# module_buzzer.net
KiCad netlist of a schematic drawn in EAGLE
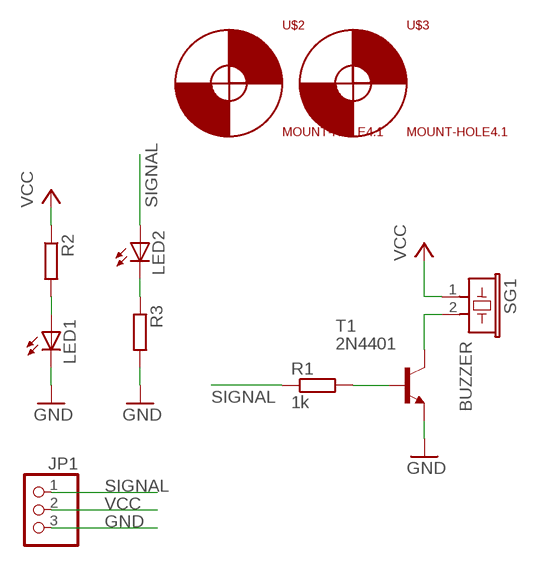
[diagram p0: schematic, sheet 1]

(export (version "E")
  (design (tool "Eeschema 10.0.6"))
  (components
    (comp (ref "JP1")
      (value "PINHD-1X3")
      (footprint "eagle-import:1X03")
      (libsource (lib "eagle-import") (part "PINHD-1X3"))
    )
    (comp (ref "LED1")
      (value "LED5MM")
      (footprint "eagle-import:LED5MM")
      (libsource (lib "eagle-import") (part "LED5MM"))
    )
    (comp (ref "LED2")
      (value "LED5MM")
      (footprint "eagle-import:LED5MM")
      (libsource (lib "eagle-import") (part "LED5MM"))
    )
    (comp (ref "R1")
      (value "1k")
      (footprint "eagle-import:0207_7")
      (libsource (lib "eagle-import") (part "R-EU_0207_7"))
    )
    (comp (ref "R2")
      (value "R-EU_0207_7")
      (footprint "eagle-import:0207_7")
      (libsource (lib "eagle-import") (part "R-EU_0207_7"))
    )
    (comp (ref "R3")
      (value "R-EU_0207_7")
      (footprint "eagle-import:0207_7")
      (libsource (lib "eagle-import") (part "R-EU_0207_7"))
    )
    (comp (ref "SG1")
      (value "BUZZER")
      (footprint "eagle-import:BUZZER-HCM1212A")
      (libsource (lib "eagle-import") (part "BUZZER"))
    )
    (comp (ref "T1")
      (value "2N4401")
      (footprint "eagle-import:TO92-CBE")
      (libsource (lib "eagle-import") (part "2N4401"))
    )
    (comp (ref "U$2")
      (value "MOUNT-HOLE4.1")
      (footprint "eagle-import:4.1")
      (libsource (lib "eagle-import") (part "MOUNT-HOLE4.1"))
    )
    (comp (ref "U$3")
      (value "MOUNT-HOLE4.1")
      (footprint "eagle-import:4.1")
      (libsource (lib "eagle-import") (part "MOUNT-HOLE4.1"))
    )
  )
  (nets
    (net (code "1") (name "/SIGNAL") (class "Default")
      (node (ref "JP1") (pin "1") (pinfunction "1_1") (pintype "passive"))
      (node (ref "LED2") (pin "A") (pinfunction "A_A") (pintype "passive"))
      (node (ref "R1") (pin "1") (pinfunction "1_1") (pintype "passive"))
    )
    (net (code "2") (name "GND") (class "Default")
      (node (ref "JP1") (pin "3") (pinfunction "3_3") (pintype "passive"))
      (node (ref "LED1") (pin "K") (pinfunction "C_K") (pintype "passive"))
      (node (ref "R3") (pin "2") (pinfunction "2_2") (pintype "passive"))
      (node (ref "T1") (pin "E") (pinfunction "E_E") (pintype "passive"))
    )
    (net (code "3") (name "Net-(LED1-PadA)") (class "Default")
      (node (ref "LED1") (pin "A") (pinfunction "A_A") (pintype "passive"))
      (node (ref "R2") (pin "2") (pinfunction "2_2") (pintype "passive"))
    )
    (net (code "4") (name "Net-(LED2-C)") (class "Default")
      (node (ref "LED2") (pin "K") (pinfunction "C_K") (pintype "passive"))
      (node (ref "R3") (pin "1") (pinfunction "1_1") (pintype "passive"))
    )
    (net (code "5") (name "Net-(R1-Pad2)") (class "Default")
      (node (ref "R1") (pin "2") (pinfunction "2_2") (pintype "passive"))
      (node (ref "T1") (pin "B") (pinfunction "B_B") (pintype "passive"))
    )
    (net (code "6") (name "Net-(SG1-Pad2)") (class "Default")
      (node (ref "SG1") (pin "2") (pinfunction "2_2") (pintype "passive"))
      (node (ref "T1") (pin "C") (pinfunction "C_C") (pintype "passive"))
    )
    (net (code "7") (name "VCC") (class "Default")
      (node (ref "JP1") (pin "2") (pinfunction "2_2") (pintype "passive"))
      (node (ref "R2") (pin "1") (pinfunction "1_1") (pintype "passive"))
      (node (ref "SG1") (pin "1") (pinfunction "1_1") (pintype "passive"))
    )
  )
)
